# Power_Ctrl.net
KiCad netlist of a schematic drawn in Altium Designer
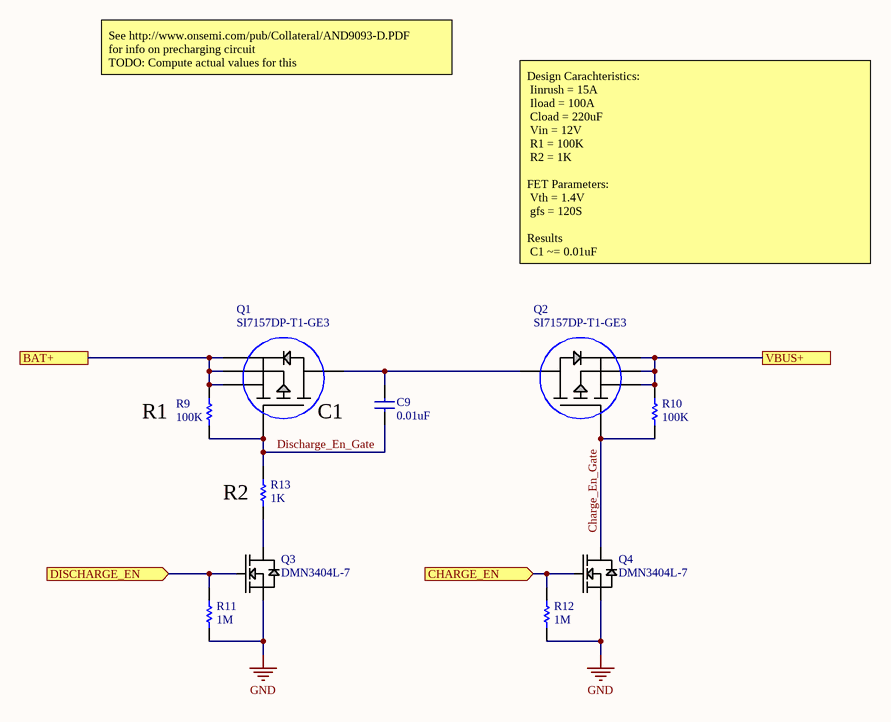
[diagram p0: Power_Ctrl.SchDoc]

(export (version "E")
  (design (tool "Eeschema 10.0.6"))
  (components
    (comp (ref "C9")
      (value "0.01uF")
      (footprint "0805_Capacitor")
      (description "CAP CERM 0.01uF 10% 50V 0805")
      (fields
        (field (name "VOLTAGE") "50V")
        (field (name "Comment") "CAP 0.01uF 50V X7R")
        (field (name "SVP CREATOR") "Spencer Berglund")
      )
      (libsource (lib "capacitor") (part "C_0805_0.01uF_50V_10%"))
    )
    (comp (ref "Q1")
      (value "SI7157DP-T1-GE3")
      (footprint "SO-8_PowerPAK(S)")
      (description "P-Channel 20V 60A (Tc) 6.25W (Ta), 104W (Tc) Surface Mount PowerPAK® SO-8")
      (libsource (lib "transistor") (part "Q_SI7157DP-T1-GE3"))
    )
    (comp (ref "Q2")
      (value "SI7157DP-T1-GE3")
      (footprint "SO-8_PowerPAK(S)")
      (description "P-Channel 20V 60A (Tc) 6.25W (Ta), 104W (Tc) Surface Mount PowerPAK® SO-8")
      (libsource (lib "transistor") (part "Q_SI7157DP-T1-GE3"))
    )
    (comp (ref "Q3")
      (value "DMN3404L-7")
      (footprint "SOT23-3")
      (description "N-Channel 30V 5.8A (Ta) 720mW (Ta) Surface Mount SOT-23-3")
      (fields (field (name "MANUFACTURER") "Diodes"))
      (libsource (lib "transistor") (part "Q_DMN3404L-7"))
    )
    (comp (ref "Q4")
      (value "DMN3404L-7")
      (footprint "SOT23-3")
      (description "N-Channel 30V 5.8A (Ta) 720mW (Ta) Surface Mount SOT-23-3")
      (fields (field (name "MANUFACTURER") "Diodes"))
      (libsource (lib "transistor") (part "Q_DMN3404L-7"))
    )
    (comp (ref "R9")
      (value "100K")
      (footprint "0603_RESISTOR")
      (description "RES 100K OHM 1/16W 1% 0603 SMD")
      (fields (field (name "Comment") "R_0603_100K_1%") (field (name "SVP CREATOR") "Spencer Berglund"))
      (libsource (lib "resistor") (part "R_0603_100K_1%"))
    )
    (comp (ref "R10")
      (value "100K")
      (footprint "0603_RESISTOR")
      (description "RES 100K OHM 1/16W 1% 0603 SMD")
      (fields (field (name "Comment") "R_0603_100K_1%") (field (name "SVP CREATOR") "Spencer Berglund"))
      (libsource (lib "resistor") (part "R_0603_100K_1%"))
    )
    (comp (ref "R11")
      (value "1M")
      (footprint "0603_RESISTOR")
      (description "RES 1M OHM 1/16W 1% 0603 SMD")
      (fields (field (name "Comment") "R_0603_1M_1%") (field (name "SVP CREATOR") "Spencer Berglund"))
      (libsource (lib "resistor") (part "R_0603_1M_1%"))
    )
    (comp (ref "R12")
      (value "1M")
      (footprint "0603_RESISTOR")
      (description "RES 1M OHM 1/16W 1% 0603 SMD")
      (fields (field (name "Comment") "R_0603_1M_1%") (field (name "SVP CREATOR") "Spencer Berglund"))
      (libsource (lib "resistor") (part "R_0603_1M_1%"))
    )
    (comp (ref "R13")
      (value "1K")
      (footprint "0603_RESISTOR")
      (description "RES 1K OHM 1/16W 1% 0603 SMD")
      (fields (field (name "Comment") "R_0603_1K_1%") (field (name "SVP CREATOR") "Spencer Berglund"))
      (libsource (lib "resistor") (part "R_0603_1K_1%"))
    )
  )
  (nets
    (net (code "1") (name "/BAT+") (class "Default")
      (node (ref "Q1") (pin "1") (pinfunction "SOURCE_1") (pintype "passive"))
      (node (ref "Q1") (pin "2") (pinfunction "SOURCE_2") (pintype "passive"))
      (node (ref "Q1") (pin "3") (pinfunction "SOURCE_3") (pintype "passive"))
      (node (ref "R9") (pin "2") (pinfunction "2_2") (pintype "passive"))
    )
    (net (code "2") (name "/CHARGE_EN") (class "Default")
      (node (ref "Q4") (pin "1") (pinfunction "GATE_1") (pintype "passive"))
      (node (ref "R12") (pin "2") (pinfunction "2_2") (pintype "passive"))
    )
    (net (code "3") (name "/Charge_En_Gate") (class "Default")
      (node (ref "Q2") (pin "4") (pinfunction "GATE_4") (pintype "passive"))
      (node (ref "Q4") (pin "3") (pinfunction "DRAIN_3") (pintype "passive"))
      (node (ref "R10") (pin "2") (pinfunction "2_2") (pintype "passive"))
    )
    (net (code "4") (name "/DISCHARGE_EN") (class "Default")
      (node (ref "Q3") (pin "1") (pinfunction "GATE_1") (pintype "passive"))
      (node (ref "R11") (pin "2") (pinfunction "2_2") (pintype "passive"))
    )
    (net (code "5") (name "/Discharge_En_Gate") (class "Default")
      (node (ref "C9") (pin "2") (pinfunction "2_2") (pintype "passive"))
      (node (ref "Q1") (pin "4") (pinfunction "GATE_4") (pintype "passive"))
      (node (ref "R13") (pin "2") (pinfunction "2_2") (pintype "passive"))
      (node (ref "R9") (pin "1") (pinfunction "1_1") (pintype "passive"))
    )
    (net (code "6") (name "/VBUS+") (class "Default")
      (node (ref "Q2") (pin "1") (pinfunction "SOURCE_1") (pintype "passive"))
      (node (ref "Q2") (pin "2") (pinfunction "SOURCE_2") (pintype "passive"))
      (node (ref "Q2") (pin "3") (pinfunction "SOURCE_3") (pintype "passive"))
      (node (ref "R10") (pin "1") (pinfunction "1_1") (pintype "passive"))
    )
    (net (code "7") (name "GND") (class "Default")
      (node (ref "Q3") (pin "2") (pinfunction "SOURCE_2") (pintype "passive"))
      (node (ref "Q4") (pin "2") (pinfunction "SOURCE_2") (pintype "passive"))
      (node (ref "R11") (pin "1") (pinfunction "1_1") (pintype "passive"))
      (node (ref "R12") (pin "1") (pinfunction "1_1") (pintype "passive"))
    )
    (net (code "8") (name "Net-(Q1-DRAIN)") (class "Default")
      (node (ref "C9") (pin "1") (pinfunction "1_1") (pintype "passive"))
      (node (ref "Q1") (pin "5") (pinfunction "DRAIN_5") (pintype "passive"))
      (node (ref "Q2") (pin "5") (pinfunction "DRAIN_5") (pintype "passive"))
    )
    (net (code "9") (name "Net-(Q3-DRAIN)") (class "Default")
      (node (ref "Q3") (pin "3") (pinfunction "DRAIN_3") (pintype "passive"))
      (node (ref "R13") (pin "1") (pinfunction "1_1") (pintype "passive"))
    )
  )
)
